# LTC6803.net
KiCad netlist of a schematic drawn in Altium Designer
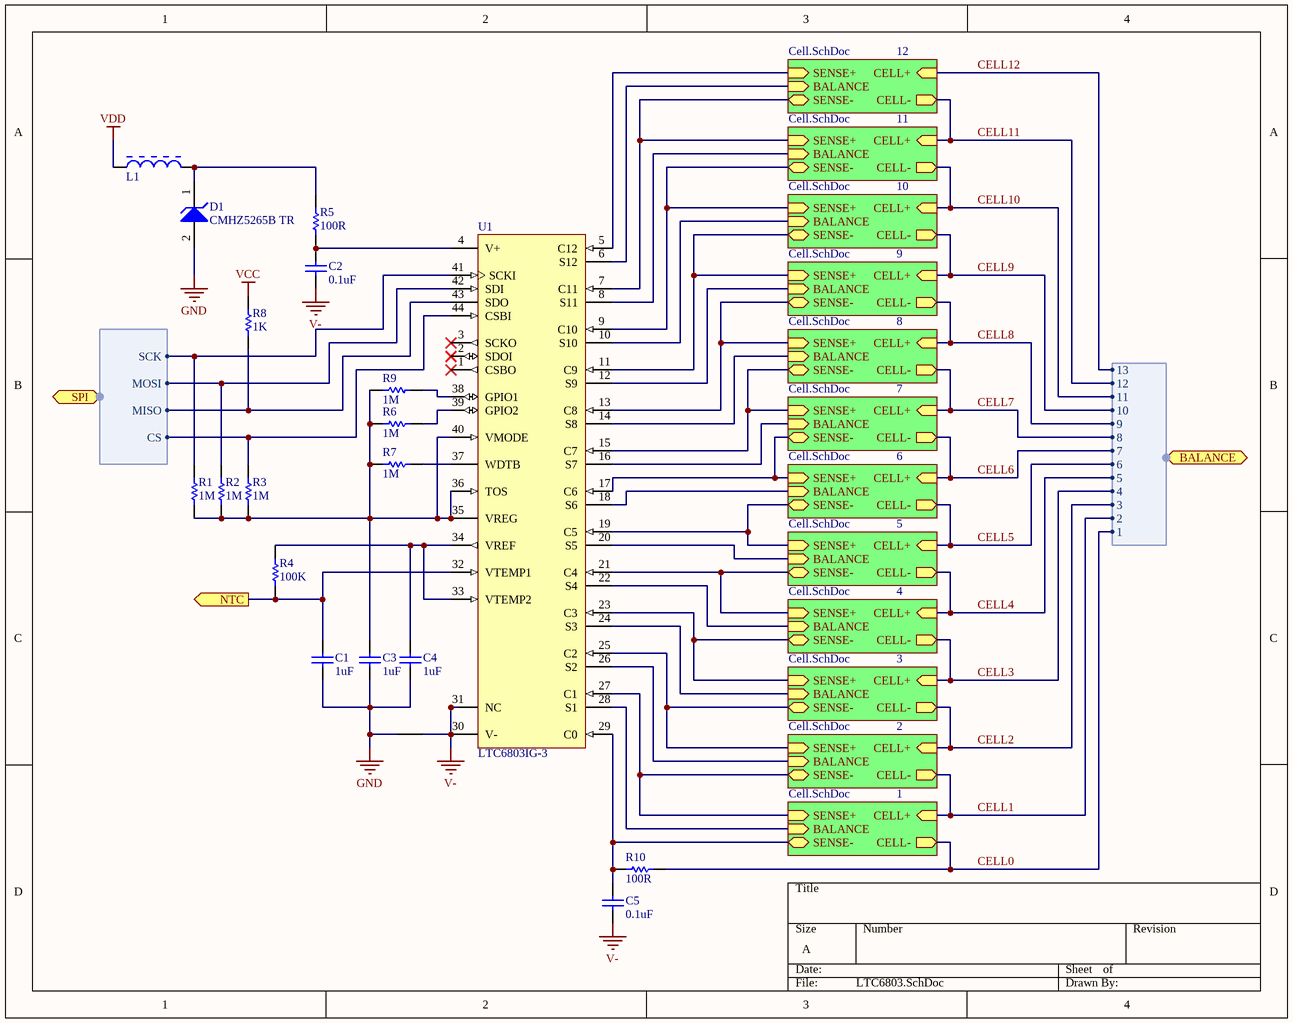
[diagram p0: LTC6803.SchDoc]

(export (version "E")
  (design (tool "Eeschema 10.0.6"))
  (components
    (comp (ref "*") (value "NetTie") (footprint "NetTie") (libsource (lib "Components") (part "NetTie")))
    (comp (ref "C1")
      (value "1uF")
      (footprint "C0402[1005X55]")
      (description "1uF 6.3V 10% 0402 (1005 Metric)")
      (fields (field (name "TOLERANCE") "10%") (field (name "PARTNUMBER") "GRM155R70J105KA12D"))
      (libsource (lib "Capacitors") (part "CAP_1uF_6.3V_0402_10%"))
    )
    (comp (ref "C2")
      (value "0.1uF")
      (footprint "C0402[1005X55]")
      (description "0.1uF 100V 10% 0402 (1005 Metric)")
      (fields (field (name "TOLERANCE") "10%") (field (name "PARTNUMBER") "GRM155R62A104KE14D"))
      (libsource (lib "Capacitors") (part "CAP_0.1uF_100V_0402_10%"))
    )
    (comp (ref "C3")
      (value "1uF")
      (footprint "C0402[1005X55]")
      (description "1uF 6.3V 10% 0402 (1005 Metric)")
      (fields (field (name "TOLERANCE") "10%") (field (name "PARTNUMBER") "GRM155R70J105KA12D"))
      (libsource (lib "Capacitors") (part "CAP_1uF_6.3V_0402_10%"))
    )
    (comp (ref "C4")
      (value "1uF")
      (footprint "C0402[1005X55]")
      (description "1uF 6.3V 10% 0402 (1005 Metric)")
      (fields (field (name "TOLERANCE") "10%") (field (name "PARTNUMBER") "GRM155R70J105KA12D"))
      (libsource (lib "Capacitors") (part "CAP_1uF_6.3V_0402_10%"))
    )
    (comp (ref "C5")
      (value "0.1uF")
      (footprint "C0402[1005X55]")
      (description "0.1uF 6.3V 10% 0402 (1005 Metric)")
      (fields (field (name "TOLERANCE") "10%") (field (name "PARTNUMBER") "GRM155R70J104KA01D"))
      (libsource (lib "Capacitors") (part "CAP_0.1uF_6.3V_0402_10%"))
    )
    (comp (ref "D1")
      (value "CMHZ5265B TR")
      (footprint "SOD-123")
      (description "Zener Diodes 500mW Zener Diode 185mA 58.9V to 2V")
      (fields (field (name "MANUFACTURER") "Central Semiconductor"))
      (libsource (lib "Diodes") (part "CMHZ5265B"))
    )
    (comp (ref "L1")
      (value "MURA-FB-2")
      (footprint "MURA-BLM31-B60-CHIP-2_V3")
      (description "EMI Filter Beads, Chips & Arrays 1206 33 OHM")
      (fields (field (name "PARTNUMBER") "BLM31PG330SN1L") (field (name "MANUFACTURER") "Murata"))
      (libsource (lib "Components") (part "MURA-FB-2"))
    )
    (comp (ref "R1")
      (value "1M")
      (footprint "R0402[1005]")
      (description "1M 0.063W 1% 0402 (1005 Metric)")
      (fields (field (name "POWER") "0.063W") (field (name "TOLERANCE") "1%"))
      (libsource (lib "Resistors") (part "RES_1M_0402_1%"))
    )
    (comp (ref "R2")
      (value "1M")
      (footprint "R0402[1005]")
      (description "1M 0.063W 1% 0402 (1005 Metric)")
      (fields (field (name "POWER") "0.063W") (field (name "TOLERANCE") "1%"))
      (libsource (lib "Resistors") (part "RES_1M_0402_1%"))
    )
    (comp (ref "R3")
      (value "1M")
      (footprint "R0402[1005]")
      (description "1M 0.063W 1% 0402 (1005 Metric)")
      (fields (field (name "POWER") "0.063W") (field (name "TOLERANCE") "1%"))
      (libsource (lib "Resistors") (part "RES_1M_0402_1%"))
    )
    (comp (ref "R4")
      (value "100K")
      (footprint "R0402[1005]")
      (description "100K 0.063W 1% 0402 (1005 Metric)")
      (fields (field (name "POWER") "0.063W") (field (name "TOLERANCE") "1%"))
      (libsource (lib "Resistors") (part "RES_100K_0402_1%"))
    )
    (comp (ref "R5")
      (value "100R")
      (footprint "R0402[1005]")
      (description "100R 0.063W 1% 0402 (1005 Metric)")
      (fields (field (name "POWER") "0.063W") (field (name "TOLERANCE") "1%"))
      (libsource (lib "Resistors") (part "RES_100R_0402_1%"))
    )
    (comp (ref "R6")
      (value "1M")
      (footprint "R0402[1005]")
      (description "1M 0.063W 1% 0402 (1005 Metric)")
      (fields (field (name "POWER") "0.063W") (field (name "TOLERANCE") "1%"))
      (libsource (lib "Resistors") (part "RES_1M_0402_1%"))
    )
    (comp (ref "R7")
      (value "1M")
      (footprint "R0402[1005]")
      (description "1M 0.063W 1% 0402 (1005 Metric)")
      (fields (field (name "POWER") "0.063W") (field (name "TOLERANCE") "1%"))
      (libsource (lib "Resistors") (part "RES_1M_0402_1%"))
    )
    (comp (ref "R8")
      (value "1K")
      (footprint "R0402[1005]")
      (description "1K 0.063W 1% 0402 (1005 Metric)")
      (fields (field (name "MANUFACTURER") "KOA Speer") (field (name "PARTNUMBER") "RK73H1ETTP1001F"))
      (libsource (lib "Resistors") (part "RES_1K_0402_1%"))
    )
    (comp (ref "R9")
      (value "1M")
      (footprint "R0402[1005]")
      (description "1M 0.063W 1% 0402 (1005 Metric)")
      (fields (field (name "POWER") "0.063W") (field (name "TOLERANCE") "1%"))
      (libsource (lib "Resistors") (part "RES_1M_0402_1%"))
    )
    (comp (ref "R10")
      (value "100R")
      (footprint "R0402[1005]")
      (description "100R 0.063W 1% 0402 (1005 Metric)")
      (fields (field (name "POWER") "0.063W") (field (name "TOLERANCE") "1%"))
      (libsource (lib "Resistors") (part "RES_100R_0402_1%"))
    )
    (comp (ref "U1")
      (value "LTC6803IG-3")
      (footprint "TSSOP-44")
      (fields (field (name "PARTNUMBER") "LTC6803IG-3#PBF") (field (name "MANUFACTURER") "Linear Technology"))
      (libsource (lib "ICs") (part "LTC6803IG-3"))
    )
  )
  (nets
    (net (code "3") (name "/BALANCE") (class "Default")
      (node (ref "U1") (pin "22") (pinfunction "S4_22") (pintype "tri_state"))
    )
    (net (code "4") (name "/BALANCE_1") (class "Default")
      (node (ref "U1") (pin "26") (pinfunction "S2_26") (pintype "tri_state"))
    )
    (net (code "5") (name "/BALANCE_2") (class "Default")
      (node (ref "U1") (pin "28") (pinfunction "S1_28") (pintype "tri_state"))
    )
    (net (code "6") (name "/BALANCE_3") (class "Default")
      (node (ref "U1") (pin "24") (pinfunction "S3_24") (pintype "tri_state"))
    )
    (net (code "7") (name "/BALANCE_4") (class "Default")
      (node (ref "U1") (pin "6") (pinfunction "S12_6") (pintype "tri_state"))
    )
    (net (code "8") (name "/BALANCE_5") (class "Default")
      (node (ref "U1") (pin "8") (pinfunction "S11_8") (pintype "tri_state"))
    )
    (net (code "9") (name "/BALANCE_6") (class "Default")
      (node (ref "U1") (pin "10") (pinfunction "S10_10") (pintype "tri_state"))
    )
    (net (code "10") (name "/BALANCE_7") (class "Default")
      (node (ref "U1") (pin "12") (pinfunction "S9_12") (pintype "tri_state"))
    )
    (net (code "11") (name "/BALANCE_8") (class "Default")
      (node (ref "U1") (pin "14") (pinfunction "S8_14") (pintype "tri_state"))
    )
    (net (code "12") (name "/BALANCE_9") (class "Default")
      (node (ref "U1") (pin "16") (pinfunction "S7_16") (pintype "tri_state"))
    )
    (net (code "13") (name "/BALANCE_10") (class "Default")
      (node (ref "U1") (pin "18") (pinfunction "S6_18") (pintype "tri_state"))
    )
    (net (code "14") (name "/BALANCE_11") (class "Default")
      (node (ref "U1") (pin "20") (pinfunction "S5_20") (pintype "tri_state"))
    )
    (net (code "15") (name "/CELL0") (class "Default")
      (node (ref "R10") (pin "2") (pinfunction "2_2") (pintype "passive"))
    )
    (net (code "28") (name "/NTC") (class "Default")
      (node (ref "C1") (pin "2") (pinfunction "2_2") (pintype "passive"))
      (node (ref "R4") (pin "1") (pinfunction "1_1") (pintype "passive"))
      (node (ref "U1") (pin "32") (pinfunction "VTEMP1_32") (pintype "input"))
    )
    (net (code "29") (name "/SENSE+") (class "Default")
      (node (ref "U1") (pin "23") (pinfunction "C3_23") (pintype "input"))
    )
    (net (code "30") (name "/SENSE+_1") (class "Default")
      (node (ref "U1") (pin "27") (pinfunction "C1_27") (pintype "input"))
    )
    (net (code "31") (name "/SENSE+_2") (class "Default")
      (node (ref "U1") (pin "25") (pinfunction "C2_25") (pintype "input"))
    )
    (net (code "32") (name "/SENSE+_3") (class "Default")
      (node (ref "U1") (pin "5") (pinfunction "C12_5") (pintype "input"))
    )
    (net (code "33") (name "/SENSE+_4") (class "Default")
      (node (ref "U1") (pin "7") (pinfunction "C11_7") (pintype "input"))
    )
    (net (code "34") (name "/SENSE+_5") (class "Default")
      (node (ref "U1") (pin "9") (pinfunction "C10_9") (pintype "input"))
    )
    (net (code "35") (name "/SENSE+_6") (class "Default")
      (node (ref "U1") (pin "11") (pinfunction "C9_11") (pintype "input"))
    )
    (net (code "36") (name "/SENSE+_7") (class "Default")
      (node (ref "U1") (pin "13") (pinfunction "C8_13") (pintype "input"))
    )
    (net (code "37") (name "/SENSE+_8") (class "Default")
      (node (ref "U1") (pin "15") (pinfunction "C7_15") (pintype "input"))
    )
    (net (code "38") (name "/SENSE+_9") (class "Default")
      (node (ref "U1") (pin "17") (pinfunction "C6_17") (pintype "input"))
    )
    (net (code "39") (name "/SENSE+_10") (class "Default")
      (node (ref "U1") (pin "19") (pinfunction "C5_19") (pintype "input"))
    )
    (net (code "40") (name "/SENSE+_11") (class "Default")
      (node (ref "U1") (pin "21") (pinfunction "C4_21") (pintype "input"))
    )
    (net (code "41") (name "/SENSE-") (class "Default")
      (node (ref "C5") (pin "2") (pinfunction "2_2") (pintype "passive"))
      (node (ref "R10") (pin "1") (pinfunction "1_1") (pintype "passive"))
      (node (ref "U1") (pin "29") (pinfunction "C0_29") (pintype "input"))
    )
    (net (code "44") (name "GND") (class "Default")
      (node (ref "*") (pin "1") (pinfunction "1_1") (pintype "passive"))
      (node (ref "C1") (pin "1") (pinfunction "1_1") (pintype "passive"))
      (node (ref "C3") (pin "1") (pinfunction "1_1") (pintype "passive"))
      (node (ref "C4") (pin "1") (pinfunction "1_1") (pintype "passive"))
      (node (ref "D1") (pin "2") (pinfunction "A_2") (pintype "passive"))
    )
    (net (code "45") (name "Net-(D1-K)") (class "Default")
      (node (ref "D1") (pin "1") (pinfunction "K_1") (pintype "passive"))
      (node (ref "L1") (pin "2") (pinfunction "2_2") (pintype "passive"))
      (node (ref "R5") (pin "2") (pinfunction "2_2") (pintype "passive"))
    )
    (net (code "46") (name "Net-(U1-CSBI)") (class "Default")
      (node (ref "R3") (pin "2") (pinfunction "2_2") (pintype "passive"))
      (node (ref "U1") (pin "44") (pinfunction "CSBI_44") (pintype "input"))
    )
    (net (code "47") (name "Net-(U1-GPIO1)") (class "Default")
      (node (ref "R9") (pin "1") (pinfunction "1_1") (pintype "passive"))
      (node (ref "U1") (pin "38") (pinfunction "GPIO1_38") (pintype "bidirectional"))
    )
    (net (code "48") (name "Net-(U1-GPIO2)") (class "Default")
      (node (ref "R6") (pin "1") (pinfunction "1_1") (pintype "passive"))
      (node (ref "U1") (pin "39") (pinfunction "GPIO2_39") (pintype "bidirectional"))
    )
    (net (code "49") (name "Net-(U1-SCKI)") (class "Default")
      (node (ref "R1") (pin "2") (pinfunction "2_2") (pintype "passive"))
      (node (ref "U1") (pin "41") (pinfunction "SCKI_41") (pintype "input"))
    )
    (net (code "50") (name "Net-(U1-SDI)") (class "Default")
      (node (ref "R2") (pin "2") (pinfunction "2_2") (pintype "passive"))
      (node (ref "U1") (pin "42") (pinfunction "SDI_42") (pintype "input"))
    )
    (net (code "51") (name "Net-(U1-SDO)") (class "Default")
      (node (ref "R8") (pin "1") (pinfunction "1_1") (pintype "passive"))
      (node (ref "U1") (pin "43") (pinfunction "SDO_43") (pintype "open_collector"))
    )
    (net (code "52") (name "Net-(U1-TOS)") (class "Default")
      (node (ref "C3") (pin "2") (pinfunction "2_2") (pintype "passive"))
      (node (ref "R1") (pin "1") (pinfunction "1_1") (pintype "passive"))
      (node (ref "R2") (pin "1") (pinfunction "1_1") (pintype "passive"))
      (node (ref "R3") (pin "1") (pinfunction "1_1") (pintype "passive"))
      (node (ref "R6") (pin "2") (pinfunction "2_2") (pintype "passive"))
      (node (ref "R7") (pin "2") (pinfunction "2_2") (pintype "passive"))
      (node (ref "R9") (pin "2") (pinfunction "2_2") (pintype "passive"))
      (node (ref "U1") (pin "35") (pinfunction "VREG_35") (pintype "power_in"))
      (node (ref "U1") (pin "36") (pinfunction "TOS_36") (pintype "input"))
      (node (ref "U1") (pin "40") (pinfunction "VMODE_40") (pintype "input"))
    )
    (net (code "53") (name "Net-(U1-V+)") (class "Default")
      (node (ref "C2") (pin "2") (pinfunction "2_2") (pintype "passive"))
      (node (ref "R5") (pin "1") (pinfunction "1_1") (pintype "passive"))
      (node (ref "U1") (pin "4") (pinfunction "V+_4") (pintype "power_in"))
    )
    (net (code "54") (name "Net-(U1-VREF)") (class "Default")
      (node (ref "C4") (pin "2") (pinfunction "2_2") (pintype "passive"))
      (node (ref "R4") (pin "2") (pinfunction "2_2") (pintype "passive"))
      (node (ref "U1") (pin "33") (pinfunction "VTEMP2_33") (pintype "input"))
      (node (ref "U1") (pin "34") (pinfunction "VREF_34") (pintype "output"))
    )
    (net (code "55") (name "Net-(U1-WDTB)") (class "Default")
      (node (ref "R7") (pin "1") (pinfunction "1_1") (pintype "passive"))
      (node (ref "U1") (pin "37") (pinfunction "WDTB_37") (pintype "open_collector"))
    )
    (net (code "56") (name "V-") (class "Default")
      (node (ref "*") (pin "2") (pinfunction "2_2") (pintype "passive"))
      (node (ref "C2") (pin "1") (pinfunction "1_1") (pintype "passive"))
      (node (ref "C5") (pin "1") (pinfunction "1_1") (pintype "passive"))
      (node (ref "U1") (pin "30") (pinfunction "V-_30") (pintype "power_in"))
      (node (ref "U1") (pin "31") (pinfunction "NC_31") (pintype "passive"))
    )
    (net (code "57") (name "VCC") (class "Default")
      (node (ref "R8") (pin "2") (pinfunction "2_2") (pintype "passive"))
    )
    (net (code "58") (name "VDD") (class "Default")
      (node (ref "L1") (pin "1") (pinfunction "1_1") (pintype "passive"))
    )
    (net (code "59") (name "unconnected-(U1-CSBO-Pad1)") (class "Default")
      (node (ref "U1") (pin "1") (pinfunction "CSBO_1") (pintype "output+no_connect"))
    )
    (net (code "60") (name "unconnected-(U1-SCKO-Pad3)") (class "Default")
      (node (ref "U1") (pin "3") (pinfunction "SCKO_3") (pintype "output+no_connect"))
    )
    (net (code "61") (name "unconnected-(U1-SDOI-Pad2)") (class "Default")
      (node (ref "U1") (pin "2") (pinfunction "SDOI_2") (pintype "bidirectional+no_connect"))
    )
  )
)
